# drum_circuits_noMIC.net
KiCad netlist of a schematic drawn in EAGLE
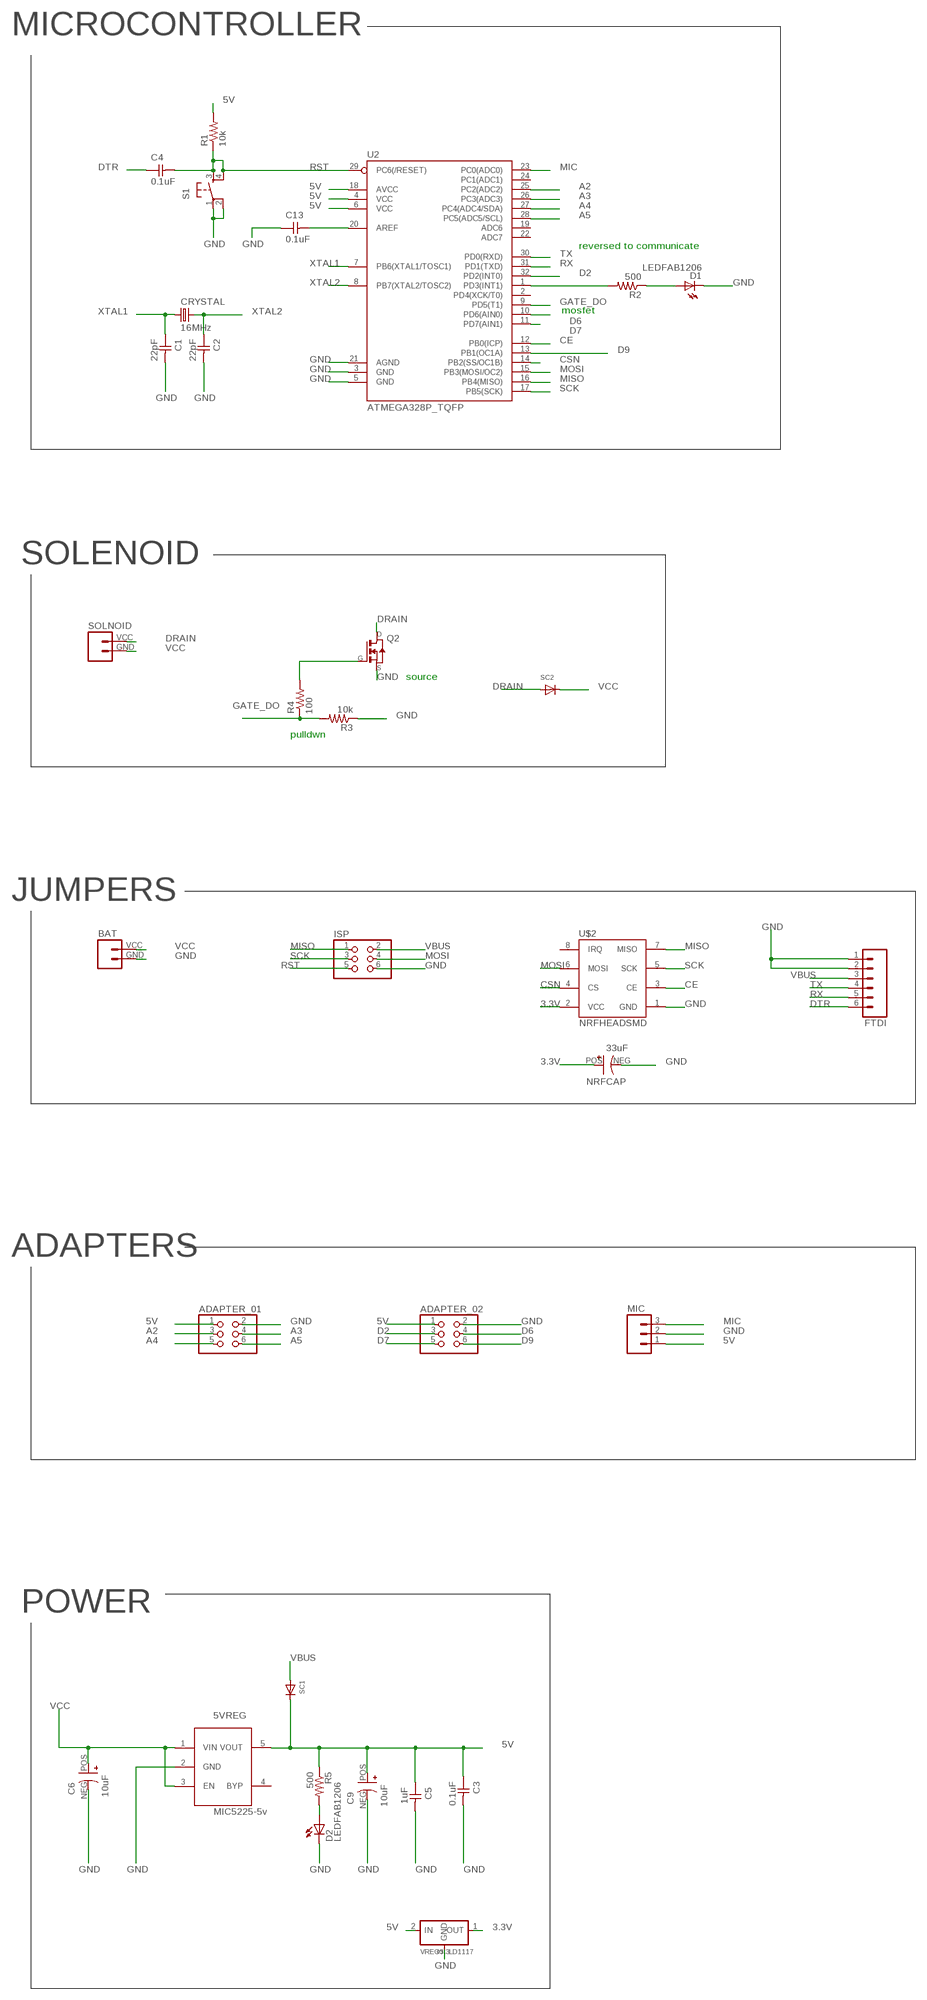
[diagram p0: schematic, sheet 1]

(export (version "E")
  (design (tool "Eeschema 10.0.6"))
  (components
    (comp (ref "5VREG")
      (value "MIC5225-5v")
      (footprint "eagle-import:SOT23-5L")
      (libsource (lib "eagle-import") (part "LP298XS"))
    )
    (comp (ref "ADAPTER_01")
      (value "PINHD-2X3-SMD")
      (footprint "eagle-import:2X03SMD")
      (libsource (lib "eagle-import") (part "PINHD-2X3-SMD"))
    )
    (comp (ref "ADAPTER_02")
      (value "PINHD-2X3-SMD")
      (footprint "eagle-import:2X03SMD")
      (libsource (lib "eagle-import") (part "PINHD-2X3-SMD"))
    )
    (comp (ref "BAT")
      (value "M024UCON-15767")
      (footprint "eagle-import:JST-2-SMD-VERT")
      (libsource (lib "eagle-import") (part "M024UCON-15767"))
    )
    (comp (ref "C1")
      (value "22pF")
      (footprint "eagle-import:C1206FAB")
      (libsource (lib "eagle-import") (part "CAP-UNPOLARIZEDFAB"))
    )
    (comp (ref "C2")
      (value "22pF")
      (footprint "eagle-import:C1206FAB")
      (libsource (lib "eagle-import") (part "CAP-UNPOLARIZEDFAB"))
    )
    (comp (ref "C3")
      (value "0.1uF")
      (footprint "eagle-import:C1206FAB")
      (libsource (lib "eagle-import") (part "CAP-UNPOLARIZEDFAB"))
    )
    (comp (ref "C4")
      (value "0.1uF")
      (footprint "eagle-import:C1206FAB")
      (libsource (lib "eagle-import") (part "CAP-UNPOLARIZEDFAB"))
    )
    (comp (ref "C5")
      (value "1uF")
      (footprint "eagle-import:C1206FAB")
      (libsource (lib "eagle-import") (part "CAP-UNPOLARIZEDFAB"))
    )
    (comp (ref "C6")
      (value "10uF")
      (footprint "eagle-import:PANASONIC-CAP-SMD-B")
      (libsource (lib "eagle-import") (part "POLCAP-PANASONIC-SMD-B01"))
    )
    (comp (ref "C9")
      (value "10uF")
      (footprint "eagle-import:PANASONIC-CAP-SMD-B")
      (libsource (lib "eagle-import") (part "POLCAP-PANASONIC-SMD-B01"))
    )
    (comp (ref "C13")
      (value "0.1uF")
      (footprint "eagle-import:C1206FAB")
      (libsource (lib "eagle-import") (part "CAP-UNPOLARIZEDFAB"))
    )
    (comp (ref "CRYSTAL")
      (value "16MHz")
      (footprint "eagle-import:2-SMD-5X3MM")
      (libsource (lib "eagle-import") (part "CRYSTAL"))
    )
    (comp (ref "D1")
      (value "LEDFAB1206")
      (footprint "eagle-import:LED1206FAB")
      (libsource (lib "eagle-import") (part "LEDFAB1206"))
    )
    (comp (ref "D2")
      (value "LEDFAB1206")
      (footprint "eagle-import:LED1206FAB")
      (libsource (lib "eagle-import") (part "LEDFAB1206"))
    )
    (comp (ref "FTDI")
      (value "M06SMD_MALE")
      (footprint "eagle-import:1X06_SMD_MALE")
      (libsource (lib "eagle-import") (part "M06SMD_MALE"))
    )
    (comp (ref "ISP")
      (value "PINHD-2X3-SMD")
      (footprint "eagle-import:2X03SMD")
      (libsource (lib "eagle-import") (part "PINHD-2X3-SMD"))
    )
    (comp (ref "MIC")
      (value "M03")
      (footprint "eagle-import:JST-3-SMD")
      (libsource (lib "eagle-import") (part "M03"))
    )
    (comp (ref "NRFCAP")
      (value "33uF")
      (footprint "eagle-import:PANASONIC-CAP-SMD-C")
      (libsource (lib "eagle-import") (part "POLCAP-PANASONIC-SMD-C"))
    )
    (comp (ref "Q2")
      (value "NMOSFETSOT23")
      (footprint "eagle-import:SOT-23")
      (libsource (lib "eagle-import") (part "NMOSFETSOT23"))
    )
    (comp (ref "R1")
      (value "10k")
      (footprint "eagle-import:R1206FAB")
      (libsource (lib "eagle-import") (part "RES-US1206FAB"))
    )
    (comp (ref "R2")
      (value "500")
      (footprint "eagle-import:R1206FAB")
      (libsource (lib "eagle-import") (part "RES-US1206FAB"))
    )
    (comp (ref "R3")
      (value "10k")
      (footprint "eagle-import:R1206FAB")
      (libsource (lib "eagle-import") (part "RES-US1206FAB"))
    )
    (comp (ref "R4")
      (value "100")
      (footprint "eagle-import:R1206FAB")
      (libsource (lib "eagle-import") (part "RES-US1206FAB"))
    )
    (comp (ref "R5")
      (value "500")
      (footprint "eagle-import:R1206FAB")
      (libsource (lib "eagle-import") (part "RES-US1206FAB"))
    )
    (comp (ref "S1")
      (value "6MM_SWITCH6MM_SWITCH")
      (footprint "eagle-import:6MM_SWITCH")
      (libsource (lib "eagle-import") (part "6MM_SWITCH6MM_SWITCH"))
    )
    (comp (ref "SC1")
      (value "DIODE_SOD-123FL")
      (footprint "eagle-import:SOD-123FL")
      (libsource (lib "eagle-import") (part "DIODE_SOD-123FL"))
    )
    (comp (ref "SC2")
      (value "DIODE_SOD-123FL")
      (footprint "eagle-import:SOD-123FL")
      (libsource (lib "eagle-import") (part "DIODE_SOD-123FL"))
    )
    (comp (ref "SOLNOID")
      (value "M024UCON-15767")
      (footprint "eagle-import:JST-2-SMD-VERT")
      (libsource (lib "eagle-import") (part "M024UCON-15767"))
    )
    (comp (ref "U$2")
      (value "NRFHEADSMD")
      (footprint "eagle-import:2.54MM")
      (libsource (lib "eagle-import") (part "NRFHEADSMD"))
    )
    (comp (ref "U2")
      (value "ATMEGA328P_TQFP")
      (footprint "eagle-import:TQFP32-08")
      (libsource (lib "eagle-import") (part "ATMEGA328P_TQFP"))
    )
    (comp (ref "VREG3.3")
      (value "LD1117")
      (footprint "eagle-import:SOT23")
      (libsource (lib "eagle-import") (part "REGULATORSOT23"))
    )
  )
  (nets
    (net (code "1") (name "/3.3V") (class "Default")
      (node (ref "NRFCAP") (pin "POS") (pinfunction "+_POS") (pintype "bidirectional"))
      (node (ref "U$2") (pin "2") (pinfunction "VCC_2") (pintype "bidirectional"))
      (node (ref "VREG3.3") (pin "1") (pinfunction "OUT_1") (pintype "bidirectional"))
    )
    (net (code "2") (name "/5V") (class "Default")
      (node (ref "5VREG") (pin "5") (pinfunction "VOUT_5") (pintype "bidirectional"))
      (node (ref "ADAPTER_01") (pin "1") (pinfunction "1_1") (pintype "passive"))
      (node (ref "ADAPTER_02") (pin "1") (pinfunction "1_1") (pintype "passive"))
      (node (ref "C3") (pin "1") (pinfunction "1_1") (pintype "passive"))
      (node (ref "C5") (pin "1") (pinfunction "1_1") (pintype "passive"))
      (node (ref "C9") (pin "POS") (pinfunction "+_POS") (pintype "bidirectional"))
      (node (ref "MIC") (pin "1") (pinfunction "1_1") (pintype "passive"))
      (node (ref "R1") (pin "2") (pinfunction "2_2") (pintype "passive"))
      (node (ref "R5") (pin "1") (pinfunction "1_1") (pintype "passive"))
      (node (ref "SC1") (pin "C") (pinfunction "C_C") (pintype "passive"))
      (node (ref "U2") (pin "18") (pinfunction "AVCC_18") (pintype "bidirectional"))
      (node (ref "U2") (pin "4") (pinfunction "VCC_4") (pintype "bidirectional"))
      (node (ref "U2") (pin "6") (pinfunction "VCC_6") (pintype "bidirectional"))
      (node (ref "VREG3.3") (pin "2") (pinfunction "IN_2") (pintype "bidirectional"))
    )
    (net (code "3") (name "/A2") (class "Default")
      (node (ref "ADAPTER_01") (pin "3") (pinfunction "3_3") (pintype "passive"))
      (node (ref "U2") (pin "25") (pinfunction "PC2(ADC2)_25") (pintype "bidirectional"))
    )
    (net (code "4") (name "/A3") (class "Default")
      (node (ref "ADAPTER_01") (pin "4") (pinfunction "4_4") (pintype "passive"))
      (node (ref "U2") (pin "26") (pinfunction "PC3(ADC3)_26") (pintype "bidirectional"))
    )
    (net (code "5") (name "/A4") (class "Default")
      (node (ref "ADAPTER_01") (pin "5") (pinfunction "5_5") (pintype "passive"))
      (node (ref "U2") (pin "27") (pinfunction "PC4(ADC4/SDA)_27") (pintype "bidirectional"))
    )
    (net (code "6") (name "/A5") (class "Default")
      (node (ref "ADAPTER_01") (pin "6") (pinfunction "6_6") (pintype "passive"))
      (node (ref "U2") (pin "28") (pinfunction "PC5(ADC5/SCL)_28") (pintype "bidirectional"))
    )
    (net (code "7") (name "/CE") (class "Default")
      (node (ref "U$2") (pin "3") (pinfunction "CE_3") (pintype "bidirectional"))
      (node (ref "U2") (pin "12") (pinfunction "PB0(ICP)_12") (pintype "bidirectional"))
    )
    (net (code "8") (name "/CSN") (class "Default")
      (node (ref "U$2") (pin "4") (pinfunction "CS_4") (pintype "bidirectional"))
      (node (ref "U2") (pin "14") (pinfunction "PB2(SS/OC1B)_14") (pintype "bidirectional"))
    )
    (net (code "9") (name "/D2") (class "Default")
      (node (ref "ADAPTER_02") (pin "3") (pinfunction "3_3") (pintype "passive"))
      (node (ref "U2") (pin "32") (pinfunction "PD2(INT0)_32") (pintype "bidirectional"))
    )
    (net (code "10") (name "/D6") (class "Default")
      (node (ref "ADAPTER_02") (pin "4") (pinfunction "4_4") (pintype "passive"))
      (node (ref "U2") (pin "10") (pinfunction "PD6(AIN0)_10") (pintype "bidirectional"))
    )
    (net (code "11") (name "/D7") (class "Default")
      (node (ref "ADAPTER_02") (pin "5") (pinfunction "5_5") (pintype "passive"))
      (node (ref "U2") (pin "11") (pinfunction "PD7(AIN1)_11") (pintype "bidirectional"))
    )
    (net (code "12") (name "/D9") (class "Default")
      (node (ref "ADAPTER_02") (pin "6") (pinfunction "6_6") (pintype "passive"))
      (node (ref "U2") (pin "13") (pinfunction "PB1(OC1A)_13") (pintype "bidirectional"))
    )
    (net (code "13") (name "/DRAIN") (class "Default")
      (node (ref "Q2") (pin "1") (pinfunction "D_1") (pintype "passive"))
      (node (ref "SC2") (pin "A") (pinfunction "A_A") (pintype "passive"))
      (node (ref "SOLNOID") (pin "VCC") (pinfunction "2_VCC") (pintype "passive"))
    )
    (net (code "14") (name "/DTR") (class "Default")
      (node (ref "C4") (pin "1") (pinfunction "1_1") (pintype "passive"))
      (node (ref "FTDI") (pin "6") (pinfunction "6_6") (pintype "passive"))
    )
    (net (code "15") (name "/GATE_DO") (class "Default")
      (node (ref "R3") (pin "2") (pinfunction "2_2") (pintype "passive"))
      (node (ref "R4") (pin "1") (pinfunction "1_1") (pintype "passive"))
      (node (ref "U2") (pin "9") (pinfunction "PD5(T1)_9") (pintype "bidirectional"))
    )
    (net (code "16") (name "/GND") (class "Default")
      (node (ref "5VREG") (pin "2") (pinfunction "GND_2") (pintype "bidirectional"))
      (node (ref "ADAPTER_01") (pin "2") (pinfunction "2_2") (pintype "passive"))
      (node (ref "ADAPTER_02") (pin "2") (pinfunction "2_2") (pintype "passive"))
      (node (ref "BAT") (pin "GND") (pinfunction "1_GND") (pintype "passive"))
      (node (ref "C1") (pin "2") (pinfunction "2_2") (pintype "passive"))
      (node (ref "C13") (pin "1") (pinfunction "1_1") (pintype "passive"))
      (node (ref "C2") (pin "2") (pinfunction "2_2") (pintype "passive"))
      (node (ref "C3") (pin "2") (pinfunction "2_2") (pintype "passive"))
      (node (ref "C5") (pin "2") (pinfunction "2_2") (pintype "passive"))
      (node (ref "C6") (pin "NEG") (pinfunction "-_NEG") (pintype "bidirectional"))
      (node (ref "C9") (pin "NEG") (pinfunction "-_NEG") (pintype "bidirectional"))
      (node (ref "D1") (pin "2") (pinfunction "C_2") (pintype "passive"))
      (node (ref "D2") (pin "2") (pinfunction "C_2") (pintype "passive"))
      (node (ref "FTDI") (pin "1") (pinfunction "1_1") (pintype "passive"))
      (node (ref "FTDI") (pin "2") (pinfunction "2_2") (pintype "passive"))
      (node (ref "ISP") (pin "6") (pinfunction "6_6") (pintype "passive"))
      (node (ref "MIC") (pin "2") (pinfunction "2_2") (pintype "passive"))
      (node (ref "NRFCAP") (pin "NEG") (pinfunction "-_NEG") (pintype "bidirectional"))
      (node (ref "Q2") (pin "2") (pinfunction "S_2") (pintype "passive"))
      (node (ref "R3") (pin "1") (pinfunction "1_1") (pintype "passive"))
      (node (ref "S1") (pin "1") (pinfunction "P_1") (pintype "passive"))
      (node (ref "S1") (pin "2") (pinfunction "P1_2") (pintype "passive"))
      (node (ref "U$2") (pin "1") (pinfunction "GND_1") (pintype "bidirectional"))
      (node (ref "U2") (pin "21") (pinfunction "AGND_21") (pintype "bidirectional"))
      (node (ref "U2") (pin "3") (pinfunction "GND_3") (pintype "bidirectional"))
      (node (ref "U2") (pin "5") (pinfunction "GND_5") (pintype "bidirectional"))
      (node (ref "VREG3.3") (pin "3") (pinfunction "GND_3") (pintype "bidirectional"))
    )
    (net (code "17") (name "/MIC") (class "Default")
      (node (ref "MIC") (pin "3") (pinfunction "3_3") (pintype "passive"))
      (node (ref "U2") (pin "23") (pinfunction "PC0(ADC0)_23") (pintype "bidirectional"))
    )
    (net (code "18") (name "/MISO") (class "Default")
      (node (ref "ISP") (pin "1") (pinfunction "1_1") (pintype "passive"))
      (node (ref "U$2") (pin "7") (pinfunction "MISO_7") (pintype "bidirectional"))
      (node (ref "U2") (pin "16") (pinfunction "PB4(MISO)_16") (pintype "bidirectional"))
    )
    (net (code "19") (name "/MOSI") (class "Default")
      (node (ref "ISP") (pin "4") (pinfunction "4_4") (pintype "passive"))
      (node (ref "U$2") (pin "6") (pinfunction "MOSI_6") (pintype "bidirectional"))
      (node (ref "U2") (pin "15") (pinfunction "PB3(MOSI/OC2)_15") (pintype "bidirectional"))
    )
    (net (code "20") (name "/RST") (class "Default")
      (node (ref "C4") (pin "2") (pinfunction "2_2") (pintype "passive"))
      (node (ref "ISP") (pin "5") (pinfunction "5_5") (pintype "passive"))
      (node (ref "R1") (pin "1") (pinfunction "1_1") (pintype "passive"))
      (node (ref "S1") (pin "3") (pinfunction "S_3") (pintype "passive"))
      (node (ref "S1") (pin "4") (pinfunction "S1_4") (pintype "passive"))
      (node (ref "U2") (pin "29") (pinfunction "PC6(/RESET)_29") (pintype "bidirectional"))
    )
    (net (code "21") (name "/RX") (class "Default")
      (node (ref "FTDI") (pin "5") (pinfunction "5_5") (pintype "passive"))
      (node (ref "U2") (pin "31") (pinfunction "PD1(TXD)_31") (pintype "bidirectional"))
    )
    (net (code "22") (name "/SCK") (class "Default")
      (node (ref "ISP") (pin "3") (pinfunction "3_3") (pintype "passive"))
      (node (ref "U$2") (pin "5") (pinfunction "SCK_5") (pintype "bidirectional"))
      (node (ref "U2") (pin "17") (pinfunction "PB5(SCK)_17") (pintype "bidirectional"))
    )
    (net (code "23") (name "/TX") (class "Default")
      (node (ref "FTDI") (pin "4") (pinfunction "4_4") (pintype "passive"))
      (node (ref "U2") (pin "30") (pinfunction "PD0(RXD)_30") (pintype "bidirectional"))
    )
    (net (code "24") (name "/VBUS") (class "Default")
      (node (ref "FTDI") (pin "3") (pinfunction "3_3") (pintype "passive"))
      (node (ref "ISP") (pin "2") (pinfunction "2_2") (pintype "passive"))
      (node (ref "SC1") (pin "A") (pinfunction "A_A") (pintype "passive"))
    )
    (net (code "25") (name "/VCC") (class "Default")
      (node (ref "5VREG") (pin "1") (pinfunction "VIN_1") (pintype "bidirectional"))
      (node (ref "5VREG") (pin "3") (pinfunction "EN_3") (pintype "bidirectional"))
      (node (ref "BAT") (pin "VCC") (pinfunction "2_VCC") (pintype "passive"))
      (node (ref "C6") (pin "POS") (pinfunction "+_POS") (pintype "bidirectional"))
      (node (ref "SC2") (pin "C") (pinfunction "C_C") (pintype "passive"))
      (node (ref "SOLNOID") (pin "GND") (pinfunction "1_GND") (pintype "passive"))
    )
    (net (code "26") (name "/XTAL1") (class "Default")
      (node (ref "C1") (pin "1") (pinfunction "1_1") (pintype "passive"))
      (node (ref "CRYSTAL") (pin "P$1") (pinfunction "1_P$1") (pintype "passive"))
      (node (ref "U2") (pin "7") (pinfunction "PB6(XTAL1/TOSC1)_7") (pintype "bidirectional"))
    )
    (net (code "27") (name "/XTAL2") (class "Default")
      (node (ref "C2") (pin "1") (pinfunction "1_1") (pintype "passive"))
      (node (ref "CRYSTAL") (pin "P$2") (pinfunction "2_P$2") (pintype "passive"))
      (node (ref "U2") (pin "8") (pinfunction "PB7(XTAL2/TOSC2)_8") (pintype "bidirectional"))
    )
    (net (code "28") (name "Net-(D1-A)") (class "Default")
      (node (ref "D1") (pin "1") (pinfunction "A_1") (pintype "passive"))
      (node (ref "R2") (pin "1") (pinfunction "1_1") (pintype "passive"))
    )
    (net (code "29") (name "Net-(D2-A)") (class "Default")
      (node (ref "D2") (pin "1") (pinfunction "A_1") (pintype "passive"))
      (node (ref "R5") (pin "2") (pinfunction "2_2") (pintype "passive"))
    )
    (net (code "30") (name "Net-(Q2-G)") (class "Default")
      (node (ref "Q2") (pin "3") (pinfunction "G_3") (pintype "passive"))
      (node (ref "R4") (pin "2") (pinfunction "2_2") (pintype "passive"))
    )
    (net (code "31") (name "Net-(U2-AREF)") (class "Default")
      (node (ref "C13") (pin "2") (pinfunction "2_2") (pintype "passive"))
      (node (ref "U2") (pin "20") (pinfunction "AREF_20") (pintype "bidirectional"))
    )
    (net (code "32") (name "Net-(U2-PD3(INT1))") (class "Default")
      (node (ref "R2") (pin "2") (pinfunction "2_2") (pintype "passive"))
      (node (ref "U2") (pin "1") (pinfunction "PD3(INT1)_1") (pintype "bidirectional"))
    )
    (net (code "33") (name "unconnected-(5VREG-BYP-Pad4)") (class "Default")
      (node (ref "5VREG") (pin "4") (pinfunction "BYP_4") (pintype "bidirectional"))
    )
    (net (code "34") (name "unconnected-(U$2-IRQ-Pad8)") (class "Default")
      (node (ref "U$2") (pin "8") (pinfunction "IRQ_8") (pintype "bidirectional"))
    )
    (net (code "35") (name "unconnected-(U2-ADC6-Pad19)") (class "Default")
      (node (ref "U2") (pin "19") (pinfunction "ADC6_19") (pintype "bidirectional"))
    )
    (net (code "36") (name "unconnected-(U2-ADC7-Pad22)") (class "Default")
      (node (ref "U2") (pin "22") (pinfunction "ADC7_22") (pintype "bidirectional"))
    )
    (net (code "37") (name "unconnected-(U2-PC1(ADC1)-Pad24)") (class "Default")
      (node (ref "U2") (pin "24") (pinfunction "PC1(ADC1)_24") (pintype "bidirectional"))
    )
    (net (code "38") (name "unconnected-(U2-PD4(XCK{slash}T0)-Pad2)") (class "Default")
      (node (ref "U2") (pin "2") (pinfunction "PD4(XCK/T0)_2") (pintype "bidirectional"))
    )
  )
)
